# SCH_cookie.net
KiCad netlist of a schematic drawn in EasyEDA
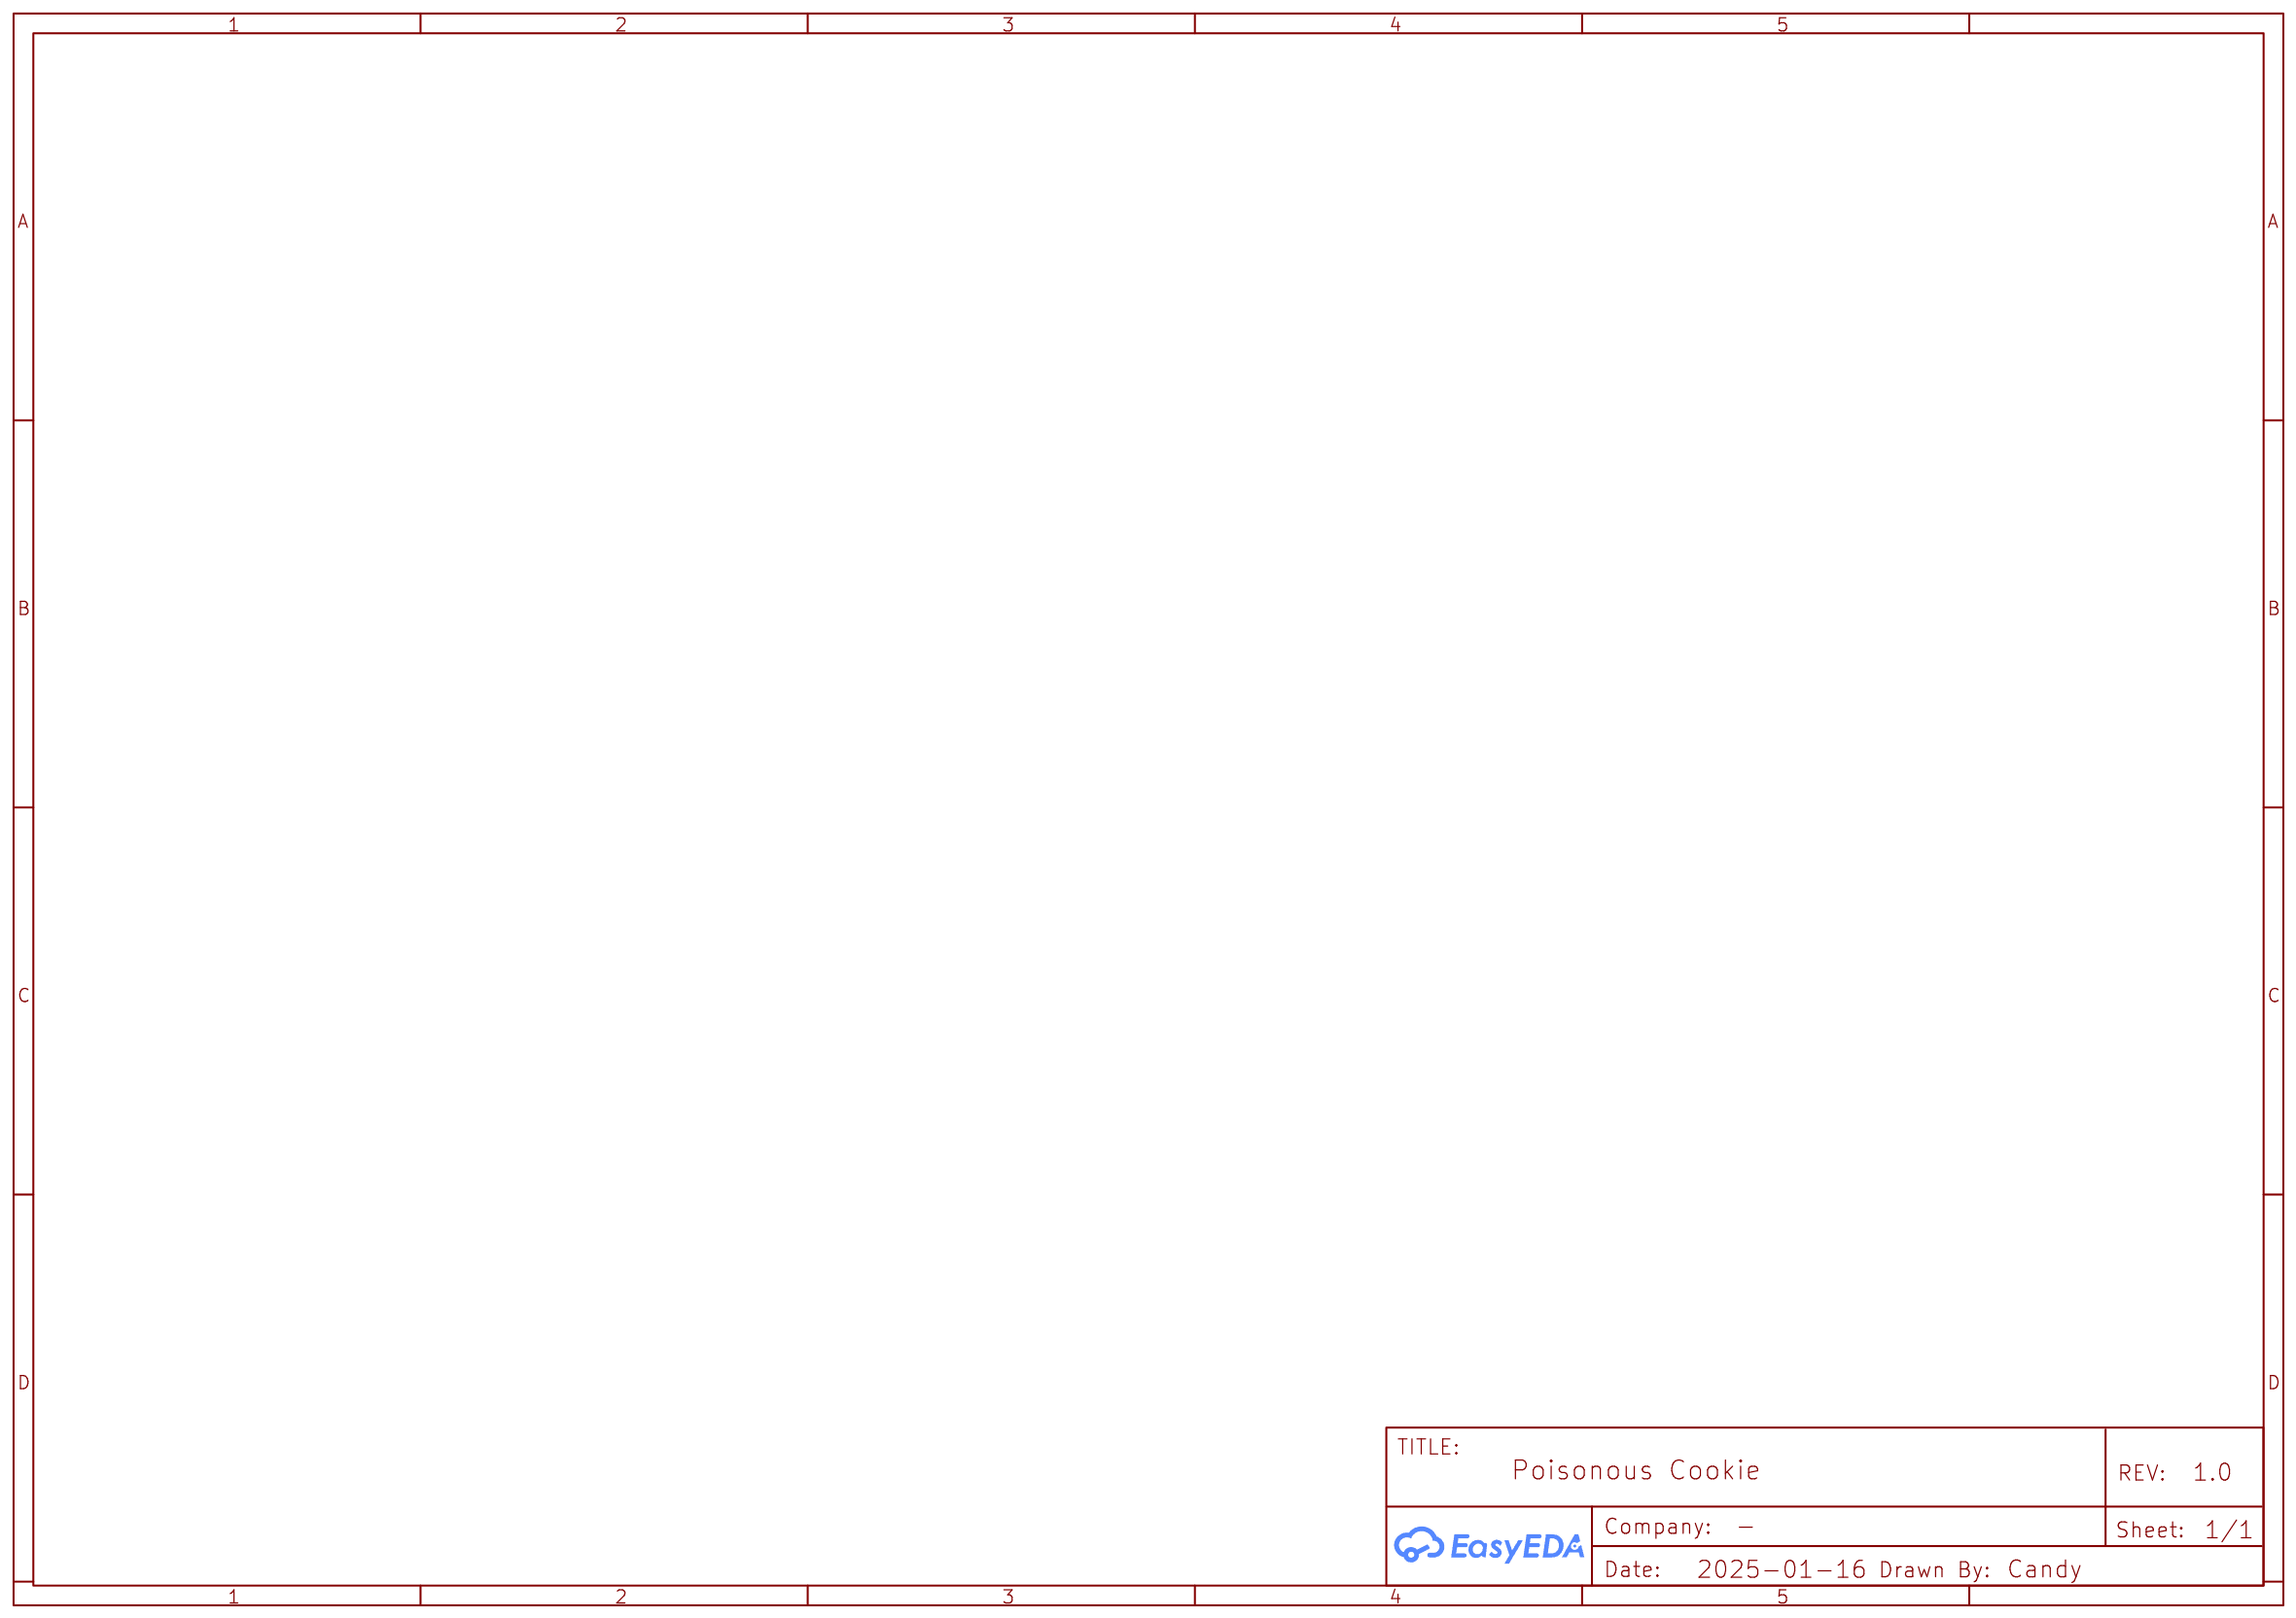
[diagram p0: Sheet_1]
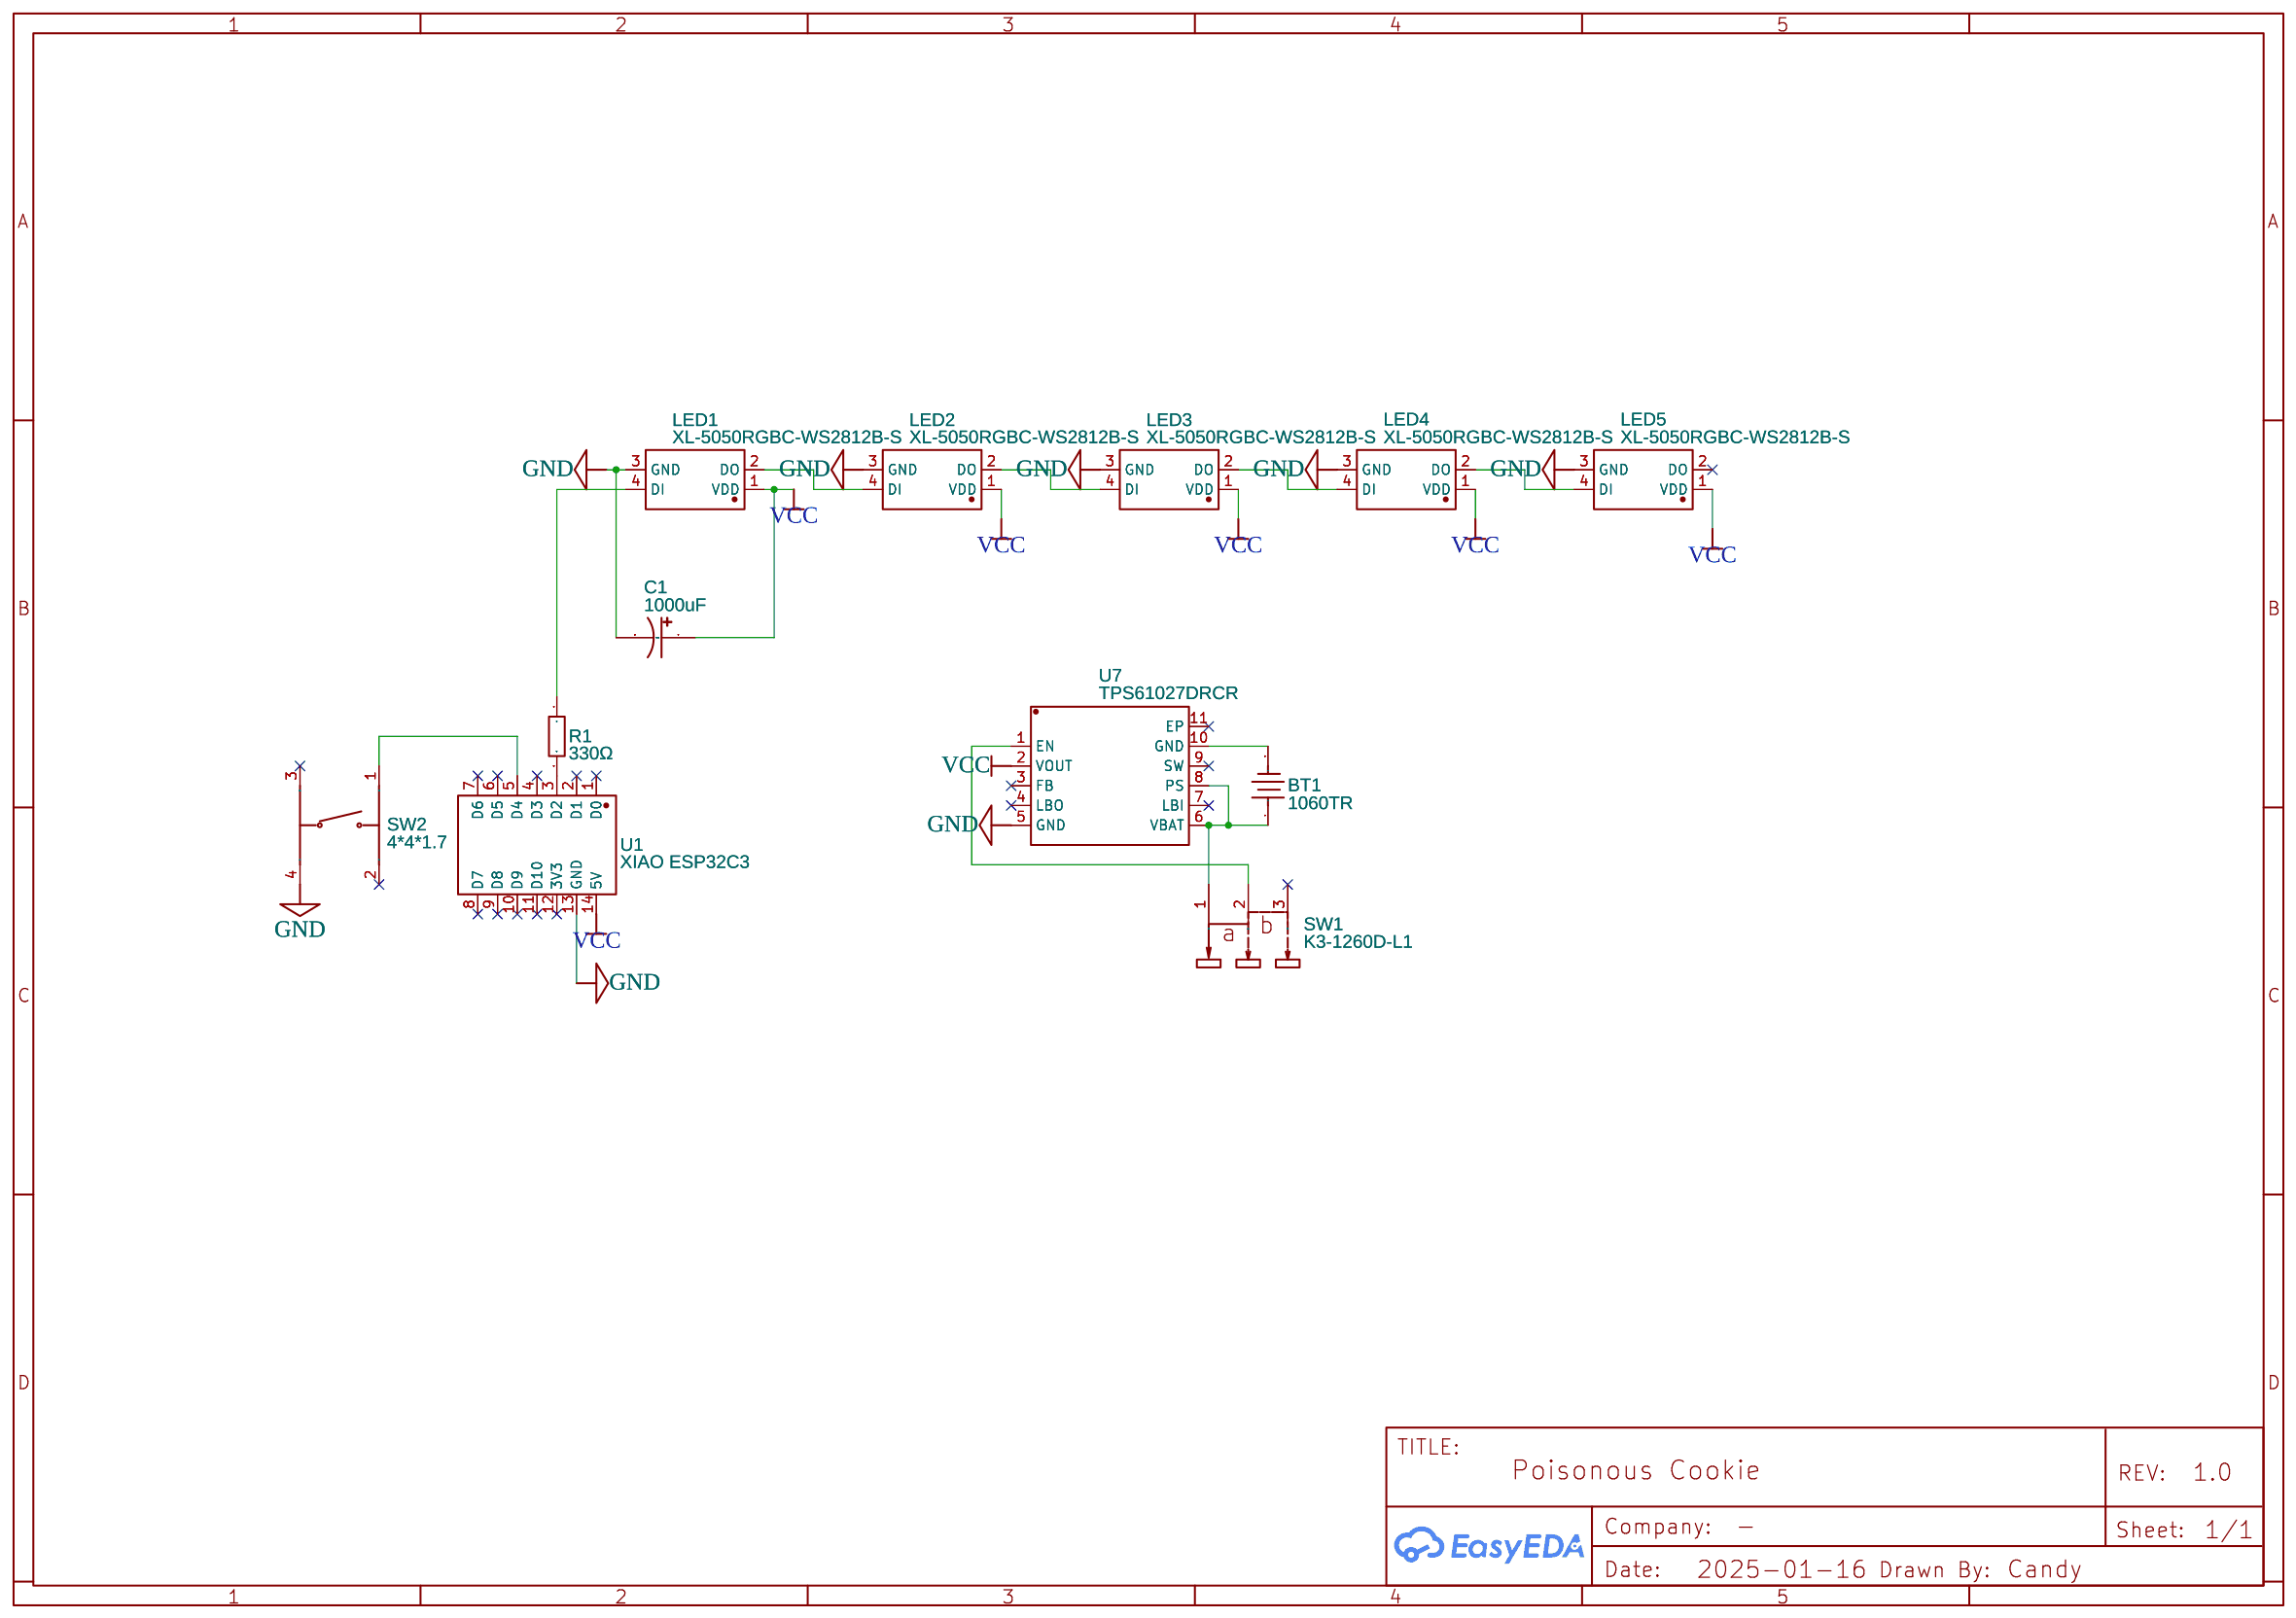
[diagram p1: rgbw]

(export (version "E")
  (design (tool "Eeschema 10.0.6"))
  (components
    (comp (ref "BT1")
      (value "1060TR")
      (fields (field (name "Manufacturer") "Keystone"))
      (libsource (lib "") (part "1060TR"))
    )
    (comp (ref "C1")
      (value "1000uF")
      (fields (field (name "Manufacturer Part") "OVZ102M0JTR-0812") (field (name "Manufacturer") "lelon(立隆)"))
      (libsource (lib "") (part "OVZ102M0J0812-TRO"))
    )
    (comp (ref "LED1")
      (value "XL-5050RGBC-WS2812B-S")
      (fields (field (name "Manufacturer") "XINGLIGHT(成兴光)"))
      (libsource (lib "") (part "XL-5050RGBC-WS2812B-S"))
    )
    (comp (ref "LED2")
      (value "XL-5050RGBC-WS2812B-S")
      (fields (field (name "Manufacturer") "XINGLIGHT(成兴光)"))
      (libsource (lib "") (part "XL-5050RGBC-WS2812B-S"))
    )
    (comp (ref "LED3")
      (value "XL-5050RGBC-WS2812B-S")
      (fields (field (name "Manufacturer") "XINGLIGHT(成兴光)"))
      (libsource (lib "") (part "XL-5050RGBC-WS2812B-S"))
    )
    (comp (ref "LED4")
      (value "XL-5050RGBC-WS2812B-S")
      (fields (field (name "Manufacturer") "XINGLIGHT(成兴光)"))
      (libsource (lib "") (part "XL-5050RGBC-WS2812B-S"))
    )
    (comp (ref "LED5")
      (value "XL-5050RGBC-WS2812B-S")
      (fields (field (name "Manufacturer") "XINGLIGHT(成兴光)"))
      (libsource (lib "") (part "XL-5050RGBC-WS2812B-S"))
    )
    (comp (ref "R1")
      (value "330Ω")
      (fields
        (field (name "Manufacturer Part") "MFR0S2F3300A20")
        (field (name "Manufacturer") "UNI-ROYAL(厚声)")
      )
      (libsource (lib "") (part "MFR0S2F3300A20"))
    )
    (comp (ref "SW1")
      (value "K3-1260D-L1")
      (fields (field (name "Manufacturer") "韩国韩荣"))
      (libsource (lib "") (part "K3-1260D-L1"))
    )
    (comp (ref "SW2")
      (value "4*4*1.7")
      (fields (field (name "Manufacturer Part") "4*4*1.7 贴片") (field (name "Manufacturer") "BOOMELE(博穆精密)"))
      (libsource (lib "") (part "4*4*1.7"))
    )
    (comp (ref "U1") (value "XIAO ESP32C3") (libsource (lib "") (part "XIAO ESP32C3")))
    (comp (ref "U7")
      (value "TPS61027DRCR")
      (fields (field (name "Manufacturer") "TI(德州仪器)"))
      (libsource (lib "") (part "TPS61027DRCR"))
    )
  )
  (nets
    (net (code "1") (name "GND") (class "Default")
      (node (ref "C1") (pin "2") (pinfunction "2_2") (pintype "unspecified"))
      (node (ref "LED1") (pin "3") (pinfunction "GND_3") (pintype "unspecified"))
      (node (ref "LED2") (pin "3") (pinfunction "GND_3") (pintype "unspecified"))
      (node (ref "LED3") (pin "3") (pinfunction "GND_3") (pintype "unspecified"))
      (node (ref "LED4") (pin "3") (pinfunction "GND_3") (pintype "unspecified"))
      (node (ref "LED5") (pin "3") (pinfunction "GND_3") (pintype "unspecified"))
      (node (ref "SW2") (pin "4") (pinfunction "4_4") (pintype "unspecified"))
      (node (ref "U1") (pin "13") (pinfunction "GND_13") (pintype "unspecified"))
      (node (ref "U7") (pin "5") (pinfunction "GND_5") (pintype "unspecified"))
    )
    (net (code "2") (name "Net-(BT1-+)") (class "Default")
      (node (ref "BT1") (pin "1") (pinfunction "+_1") (pintype "unspecified"))
      (node (ref "SW1") (pin "1") (pinfunction "1_1") (pintype "unspecified"))
      (node (ref "U7") (pin "6") (pinfunction "VBAT_6") (pintype "unspecified"))
      (node (ref "U7") (pin "8") (pinfunction "PS_8") (pintype "unspecified"))
    )
    (net (code "3") (name "Net-(BT1--)") (class "Default")
      (node (ref "BT1") (pin "2") (pinfunction "-_2") (pintype "unspecified"))
      (node (ref "U7") (pin "10") (pinfunction "GND_10") (pintype "unspecified"))
    )
    (net (code "4") (name "Net-(LED1-DI)") (class "Default")
      (node (ref "LED1") (pin "4") (pinfunction "DI_4") (pintype "unspecified"))
      (node (ref "R1") (pin "1") (pinfunction "1_1") (pintype "input"))
    )
    (net (code "5") (name "Net-(LED1-DO)") (class "Default")
      (node (ref "LED1") (pin "2") (pinfunction "DO_2") (pintype "unspecified"))
      (node (ref "LED2") (pin "4") (pinfunction "DI_4") (pintype "unspecified"))
    )
    (net (code "6") (name "Net-(LED2-DO)") (class "Default")
      (node (ref "LED2") (pin "2") (pinfunction "DO_2") (pintype "unspecified"))
      (node (ref "LED3") (pin "4") (pinfunction "DI_4") (pintype "unspecified"))
    )
    (net (code "7") (name "Net-(LED3-DO)") (class "Default")
      (node (ref "LED3") (pin "2") (pinfunction "DO_2") (pintype "unspecified"))
      (node (ref "LED4") (pin "4") (pinfunction "DI_4") (pintype "unspecified"))
    )
    (net (code "8") (name "Net-(LED4-DO)") (class "Default")
      (node (ref "LED4") (pin "2") (pinfunction "DO_2") (pintype "unspecified"))
      (node (ref "LED5") (pin "4") (pinfunction "DI_4") (pintype "unspecified"))
    )
    (net (code "9") (name "Net-(U1-D2)") (class "Default")
      (node (ref "R1") (pin "2") (pinfunction "2_2") (pintype "input"))
      (node (ref "U1") (pin "3") (pinfunction "D2_3") (pintype "unspecified"))
    )
    (net (code "10") (name "Net-(U1-D4)") (class "Default")
      (node (ref "SW2") (pin "1") (pinfunction "1_1") (pintype "unspecified"))
      (node (ref "U1") (pin "5") (pinfunction "D4_5") (pintype "unspecified"))
    )
    (net (code "11") (name "Net-(U7-EN)") (class "Default")
      (node (ref "SW1") (pin "2") (pinfunction "2_2") (pintype "unspecified"))
      (node (ref "U7") (pin "1") (pinfunction "EN_1") (pintype "unspecified"))
    )
    (net (code "12") (name "VCC") (class "Default")
      (node (ref "C1") (pin "1") (pinfunction "1_1") (pintype "unspecified"))
      (node (ref "LED1") (pin "1") (pinfunction "VDD_1") (pintype "unspecified"))
      (node (ref "LED2") (pin "1") (pinfunction "VDD_1") (pintype "unspecified"))
      (node (ref "LED3") (pin "1") (pinfunction "VDD_1") (pintype "unspecified"))
      (node (ref "LED4") (pin "1") (pinfunction "VDD_1") (pintype "unspecified"))
      (node (ref "LED5") (pin "1") (pinfunction "VDD_1") (pintype "unspecified"))
      (node (ref "U1") (pin "14") (pinfunction "5V_14") (pintype "unspecified"))
      (node (ref "U7") (pin "2") (pinfunction "VOUT_2") (pintype "unspecified"))
    )
    (net (code "13") (name "unconnected-(LED5-DO-Pad2)") (class "Default")
      (node (ref "LED5") (pin "2") (pinfunction "DO_2") (pintype "unspecified+no_connect"))
    )
    (net (code "14") (name "unconnected-(SW1-Pad3)") (class "Default")
      (node (ref "SW1") (pin "3") (pinfunction "3_3") (pintype "unspecified+no_connect"))
    )
    (net (code "15") (name "unconnected-(SW2-Pad2)") (class "Default")
      (node (ref "SW2") (pin "2") (pinfunction "2_2") (pintype "unspecified+no_connect"))
    )
    (net (code "16") (name "unconnected-(SW2-Pad3)") (class "Default")
      (node (ref "SW2") (pin "3") (pinfunction "3_3") (pintype "unspecified+no_connect"))
    )
    (net (code "17") (name "unconnected-(U1-3V3-Pad12)") (class "Default")
      (node (ref "U1") (pin "12") (pinfunction "3V3_12") (pintype "unspecified+no_connect"))
    )
    (net (code "18") (name "unconnected-(U1-D0-Pad1)") (class "Default")
      (node (ref "U1") (pin "1") (pinfunction "D0_1") (pintype "unspecified+no_connect"))
    )
    (net (code "19") (name "unconnected-(U1-D1-Pad2)") (class "Default")
      (node (ref "U1") (pin "2") (pinfunction "D1_2") (pintype "unspecified+no_connect"))
    )
    (net (code "20") (name "unconnected-(U1-D3-Pad4)") (class "Default")
      (node (ref "U1") (pin "4") (pinfunction "D3_4") (pintype "unspecified+no_connect"))
    )
    (net (code "21") (name "unconnected-(U1-D5-Pad6)") (class "Default")
      (node (ref "U1") (pin "6") (pinfunction "D5_6") (pintype "unspecified+no_connect"))
    )
    (net (code "22") (name "unconnected-(U1-D6-Pad7)") (class "Default")
      (node (ref "U1") (pin "7") (pinfunction "D6_7") (pintype "unspecified+no_connect"))
    )
    (net (code "23") (name "unconnected-(U1-D7-Pad8)") (class "Default")
      (node (ref "U1") (pin "8") (pinfunction "D7_8") (pintype "unspecified+no_connect"))
    )
    (net (code "24") (name "unconnected-(U1-D8-Pad9)") (class "Default")
      (node (ref "U1") (pin "9") (pinfunction "D8_9") (pintype "unspecified+no_connect"))
    )
    (net (code "25") (name "unconnected-(U1-D9-Pad10)") (class "Default")
      (node (ref "U1") (pin "10") (pinfunction "D9_10") (pintype "unspecified+no_connect"))
    )
    (net (code "26") (name "unconnected-(U1-D10-Pad11)") (class "Default")
      (node (ref "U1") (pin "11") (pinfunction "D10_11") (pintype "unspecified+no_connect"))
    )
    (net (code "27") (name "unconnected-(U7-EP-Pad11)") (class "Default")
      (node (ref "U7") (pin "11") (pinfunction "EP_11") (pintype "unspecified+no_connect"))
    )
    (net (code "28") (name "unconnected-(U7-FB-Pad3)") (class "Default")
      (node (ref "U7") (pin "3") (pinfunction "FB_3") (pintype "unspecified+no_connect"))
    )
    (net (code "29") (name "unconnected-(U7-LBI-Pad7)") (class "Default")
      (node (ref "U7") (pin "7") (pinfunction "LBI_7") (pintype "unspecified+no_connect"))
    )
    (net (code "30") (name "unconnected-(U7-LBO-Pad4)") (class "Default")
      (node (ref "U7") (pin "4") (pinfunction "LBO_4") (pintype "unspecified+no_connect"))
    )
    (net (code "31") (name "unconnected-(U7-SW-Pad9)") (class "Default")
      (node (ref "U7") (pin "9") (pinfunction "SW_9") (pintype "unspecified+no_connect"))
    )
  )
)
